# main.net
KiCad netlist of a schematic drawn in Altium Designer
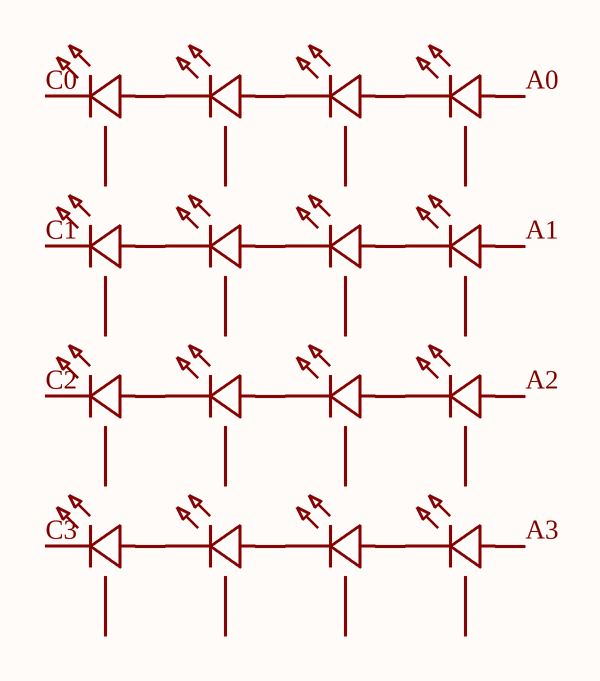
[diagram p0: main.SchDoc]

(export (version "E")
  (design (tool "Eeschema 10.0.6"))
  (components
    (comp (ref "U1")
      (value "XL-C3570P8S11-62C3C2")
      (footprint "LED-SMD_3P-L7.0-W3.5_XL-C3570P5S10-62C3C2")
      (fields (field (name "BOM_SUPPLIER PART") "C3646958") (field (name "CONTRIBUTOR") "lcsc"))
      (libsource (lib "altium-import") (part "root_0_XL-C3570P8S11-62C3C2_"))
    )
    (comp (ref "U2")
      (value "XL-C3570P8S11-62C3C2")
      (footprint "LED-SMD_3P-L7.0-W3.5_XL-C3570P5S10-62C3C2")
      (fields (field (name "BOM_SUPPLIER PART") "C3646958") (field (name "CONTRIBUTOR") "lcsc"))
      (libsource (lib "altium-import") (part "root_0_XL-C3570P8S11-62C3C2_"))
    )
    (comp (ref "U3")
      (value "XL-C3570P8S11-62C3C2")
      (footprint "LED-SMD_3P-L7.0-W3.5_XL-C3570P5S10-62C3C2")
      (fields (field (name "BOM_SUPPLIER PART") "C3646958") (field (name "CONTRIBUTOR") "lcsc"))
      (libsource (lib "altium-import") (part "root_0_XL-C3570P8S11-62C3C2_"))
    )
    (comp (ref "U4")
      (value "XL-C3570P8S11-62C3C2")
      (footprint "LED-SMD_3P-L7.0-W3.5_XL-C3570P5S10-62C3C2")
      (fields (field (name "BOM_SUPPLIER PART") "C3646958") (field (name "CONTRIBUTOR") "lcsc"))
      (libsource (lib "altium-import") (part "root_0_XL-C3570P8S11-62C3C2_"))
    )
    (comp (ref "U5")
      (value "XL-C3570P8S11-62C3C2")
      (footprint "LED-SMD_3P-L7.0-W3.5_XL-C3570P5S10-62C3C2")
      (fields (field (name "BOM_SUPPLIER PART") "C3646958") (field (name "CONTRIBUTOR") "lcsc"))
      (libsource (lib "altium-import") (part "root_0_XL-C3570P8S11-62C3C2_"))
    )
    (comp (ref "U6")
      (value "XL-C3570P8S11-62C3C2")
      (footprint "LED-SMD_3P-L7.0-W3.5_XL-C3570P5S10-62C3C2")
      (fields (field (name "BOM_SUPPLIER PART") "C3646958") (field (name "CONTRIBUTOR") "lcsc"))
      (libsource (lib "altium-import") (part "root_0_XL-C3570P8S11-62C3C2_"))
    )
    (comp (ref "U7")
      (value "XL-C3570P8S11-62C3C2")
      (footprint "LED-SMD_3P-L7.0-W3.5_XL-C3570P5S10-62C3C2")
      (fields (field (name "BOM_SUPPLIER PART") "C3646958") (field (name "CONTRIBUTOR") "lcsc"))
      (libsource (lib "altium-import") (part "root_0_XL-C3570P8S11-62C3C2_"))
    )
    (comp (ref "U8")
      (value "XL-C3570P8S11-62C3C2")
      (footprint "LED-SMD_3P-L7.0-W3.5_XL-C3570P5S10-62C3C2")
      (fields (field (name "BOM_SUPPLIER PART") "C3646958") (field (name "CONTRIBUTOR") "lcsc"))
      (libsource (lib "altium-import") (part "root_0_XL-C3570P8S11-62C3C2_"))
    )
    (comp (ref "U9")
      (value "XL-C3570P8S11-62C3C2")
      (footprint "LED-SMD_3P-L7.0-W3.5_XL-C3570P5S10-62C3C2")
      (fields (field (name "BOM_SUPPLIER PART") "C3646958") (field (name "CONTRIBUTOR") "lcsc"))
      (libsource (lib "altium-import") (part "root_0_XL-C3570P8S11-62C3C2_"))
    )
    (comp (ref "U10")
      (value "XL-C3570P8S11-62C3C2")
      (footprint "LED-SMD_3P-L7.0-W3.5_XL-C3570P5S10-62C3C2")
      (fields (field (name "BOM_SUPPLIER PART") "C3646958") (field (name "CONTRIBUTOR") "lcsc"))
      (libsource (lib "altium-import") (part "root_0_XL-C3570P8S11-62C3C2_"))
    )
    (comp (ref "U11")
      (value "XL-C3570P8S11-62C3C2")
      (footprint "LED-SMD_3P-L7.0-W3.5_XL-C3570P5S10-62C3C2")
      (fields (field (name "BOM_SUPPLIER PART") "C3646958") (field (name "CONTRIBUTOR") "lcsc"))
      (libsource (lib "altium-import") (part "root_0_XL-C3570P8S11-62C3C2_"))
    )
    (comp (ref "U12")
      (value "XL-C3570P8S11-62C3C2")
      (footprint "LED-SMD_3P-L7.0-W3.5_XL-C3570P5S10-62C3C2")
      (fields (field (name "BOM_SUPPLIER PART") "C3646958") (field (name "CONTRIBUTOR") "lcsc"))
      (libsource (lib "altium-import") (part "root_0_XL-C3570P8S11-62C3C2_"))
    )
    (comp (ref "U13")
      (value "XL-C3570P8S11-62C3C2")
      (footprint "LED-SMD_3P-L7.0-W3.5_XL-C3570P5S10-62C3C2")
      (fields (field (name "BOM_SUPPLIER PART") "C3646958") (field (name "CONTRIBUTOR") "lcsc"))
      (libsource (lib "altium-import") (part "root_0_XL-C3570P8S11-62C3C2_"))
    )
    (comp (ref "U14")
      (value "XL-C3570P8S11-62C3C2")
      (footprint "LED-SMD_3P-L7.0-W3.5_XL-C3570P5S10-62C3C2")
      (fields (field (name "BOM_SUPPLIER PART") "C3646958") (field (name "CONTRIBUTOR") "lcsc"))
      (libsource (lib "altium-import") (part "root_0_XL-C3570P8S11-62C3C2_"))
    )
    (comp (ref "U15")
      (value "XL-C3570P8S11-62C3C2")
      (footprint "LED-SMD_3P-L7.0-W3.5_XL-C3570P5S10-62C3C2")
      (fields (field (name "BOM_SUPPLIER PART") "C3646958") (field (name "CONTRIBUTOR") "lcsc"))
      (libsource (lib "altium-import") (part "root_0_XL-C3570P8S11-62C3C2_"))
    )
    (comp (ref "U16")
      (value "XL-C3570P8S11-62C3C2")
      (footprint "LED-SMD_3P-L7.0-W3.5_XL-C3570P5S10-62C3C2")
      (fields (field (name "BOM_SUPPLIER PART") "C3646958") (field (name "CONTRIBUTOR") "lcsc"))
      (libsource (lib "altium-import") (part "root_0_XL-C3570P8S11-62C3C2_"))
    )
  )
  (nets
    (net (code "1") (name "/A0") (class "Default")
      (node (ref "U4") (pin "3") (pinfunction "A_3") (pintype "passive"))
    )
    (net (code "2") (name "/A1") (class "Default")
      (node (ref "U8") (pin "3") (pinfunction "A_3") (pintype "passive"))
    )
    (net (code "3") (name "/A2") (class "Default")
      (node (ref "U12") (pin "3") (pinfunction "A_3") (pintype "passive"))
    )
    (net (code "4") (name "/A3") (class "Default")
      (node (ref "U16") (pin "3") (pinfunction "A_3") (pintype "passive"))
    )
    (net (code "5") (name "/C0") (class "Default")
      (node (ref "U1") (pin "1") (pinfunction "K_1") (pintype "passive"))
    )
    (net (code "6") (name "/C1") (class "Default")
      (node (ref "U5") (pin "1") (pinfunction "K_1") (pintype "passive"))
    )
    (net (code "7") (name "/C2") (class "Default")
      (node (ref "U9") (pin "1") (pinfunction "K_1") (pintype "passive"))
    )
    (net (code "8") (name "/C3") (class "Default")
      (node (ref "U13") (pin "1") (pinfunction "K_1") (pintype "passive"))
    )
    (net (code "9") (name "Net-(U1-A)") (class "Default")
      (node (ref "U1") (pin "3") (pinfunction "A_3") (pintype "passive"))
      (node (ref "U2") (pin "1") (pinfunction "K_1") (pintype "passive"))
    )
    (net (code "10") (name "Net-(U2-A)") (class "Default")
      (node (ref "U2") (pin "3") (pinfunction "A_3") (pintype "passive"))
      (node (ref "U3") (pin "1") (pinfunction "K_1") (pintype "passive"))
    )
    (net (code "11") (name "Net-(U3-A)") (class "Default")
      (node (ref "U3") (pin "3") (pinfunction "A_3") (pintype "passive"))
      (node (ref "U4") (pin "1") (pinfunction "K_1") (pintype "passive"))
    )
    (net (code "12") (name "Net-(U5-A)") (class "Default")
      (node (ref "U5") (pin "3") (pinfunction "A_3") (pintype "passive"))
      (node (ref "U6") (pin "1") (pinfunction "K_1") (pintype "passive"))
    )
    (net (code "13") (name "Net-(U6-A)") (class "Default")
      (node (ref "U6") (pin "3") (pinfunction "A_3") (pintype "passive"))
      (node (ref "U7") (pin "1") (pinfunction "K_1") (pintype "passive"))
    )
    (net (code "14") (name "Net-(U7-A)") (class "Default")
      (node (ref "U7") (pin "3") (pinfunction "A_3") (pintype "passive"))
      (node (ref "U8") (pin "1") (pinfunction "K_1") (pintype "passive"))
    )
    (net (code "15") (name "Net-(U10-A)") (class "Default")
      (node (ref "U10") (pin "3") (pinfunction "A_3") (pintype "passive"))
      (node (ref "U11") (pin "1") (pinfunction "K_1") (pintype "passive"))
    )
    (net (code "16") (name "Net-(U10-K)") (class "Default")
      (node (ref "U10") (pin "1") (pinfunction "K_1") (pintype "passive"))
      (node (ref "U9") (pin "3") (pinfunction "A_3") (pintype "passive"))
    )
    (net (code "17") (name "Net-(U11-A)") (class "Default")
      (node (ref "U11") (pin "3") (pinfunction "A_3") (pintype "passive"))
      (node (ref "U12") (pin "1") (pinfunction "K_1") (pintype "passive"))
    )
    (net (code "18") (name "Net-(U13-A)") (class "Default")
      (node (ref "U13") (pin "3") (pinfunction "A_3") (pintype "passive"))
      (node (ref "U14") (pin "1") (pinfunction "K_1") (pintype "passive"))
    )
    (net (code "19") (name "Net-(U14-A)") (class "Default")
      (node (ref "U14") (pin "3") (pinfunction "A_3") (pintype "passive"))
      (node (ref "U15") (pin "1") (pinfunction "K_1") (pintype "passive"))
    )
    (net (code "20") (name "Net-(U15-A)") (class "Default")
      (node (ref "U15") (pin "3") (pinfunction "A_3") (pintype "passive"))
      (node (ref "U16") (pin "1") (pinfunction "K_1") (pintype "passive"))
    )
    (net (code "21") (name "unconnected-(U1-D-Pad2)") (class "Default")
      (node (ref "U1") (pin "2") (pinfunction "D_2") (pintype "passive"))
    )
    (net (code "22") (name "unconnected-(U2-D-Pad2)") (class "Default")
      (node (ref "U2") (pin "2") (pinfunction "D_2") (pintype "passive"))
    )
    (net (code "23") (name "unconnected-(U3-D-Pad2)") (class "Default")
      (node (ref "U3") (pin "2") (pinfunction "D_2") (pintype "passive"))
    )
    (net (code "24") (name "unconnected-(U4-D-Pad2)") (class "Default")
      (node (ref "U4") (pin "2") (pinfunction "D_2") (pintype "passive"))
    )
    (net (code "25") (name "unconnected-(U5-D-Pad2)") (class "Default")
      (node (ref "U5") (pin "2") (pinfunction "D_2") (pintype "passive"))
    )
    (net (code "26") (name "unconnected-(U6-D-Pad2)") (class "Default")
      (node (ref "U6") (pin "2") (pinfunction "D_2") (pintype "passive"))
    )
    (net (code "27") (name "unconnected-(U7-D-Pad2)") (class "Default")
      (node (ref "U7") (pin "2") (pinfunction "D_2") (pintype "passive"))
    )
    (net (code "28") (name "unconnected-(U8-D-Pad2)") (class "Default")
      (node (ref "U8") (pin "2") (pinfunction "D_2") (pintype "passive"))
    )
    (net (code "29") (name "unconnected-(U9-D-Pad2)") (class "Default")
      (node (ref "U9") (pin "2") (pinfunction "D_2") (pintype "passive"))
    )
    (net (code "30") (name "unconnected-(U10-D-Pad2)") (class "Default")
      (node (ref "U10") (pin "2") (pinfunction "D_2") (pintype "passive"))
    )
    (net (code "31") (name "unconnected-(U11-D-Pad2)") (class "Default")
      (node (ref "U11") (pin "2") (pinfunction "D_2") (pintype "passive"))
    )
    (net (code "32") (name "unconnected-(U12-D-Pad2)") (class "Default")
      (node (ref "U12") (pin "2") (pinfunction "D_2") (pintype "passive"))
    )
    (net (code "33") (name "unconnected-(U13-D-Pad2)") (class "Default")
      (node (ref "U13") (pin "2") (pinfunction "D_2") (pintype "passive"))
    )
    (net (code "34") (name "unconnected-(U14-D-Pad2)") (class "Default")
      (node (ref "U14") (pin "2") (pinfunction "D_2") (pintype "passive"))
    )
    (net (code "35") (name "unconnected-(U15-D-Pad2)") (class "Default")
      (node (ref "U15") (pin "2") (pinfunction "D_2") (pintype "passive"))
    )
    (net (code "36") (name "unconnected-(U16-D-Pad2)") (class "Default")
      (node (ref "U16") (pin "2") (pinfunction "D_2") (pintype "passive"))
    )
  )
)
